# SCH_BlackboxHub_2024-05-23.net
KiCad netlist of a schematic drawn in EasyEDA
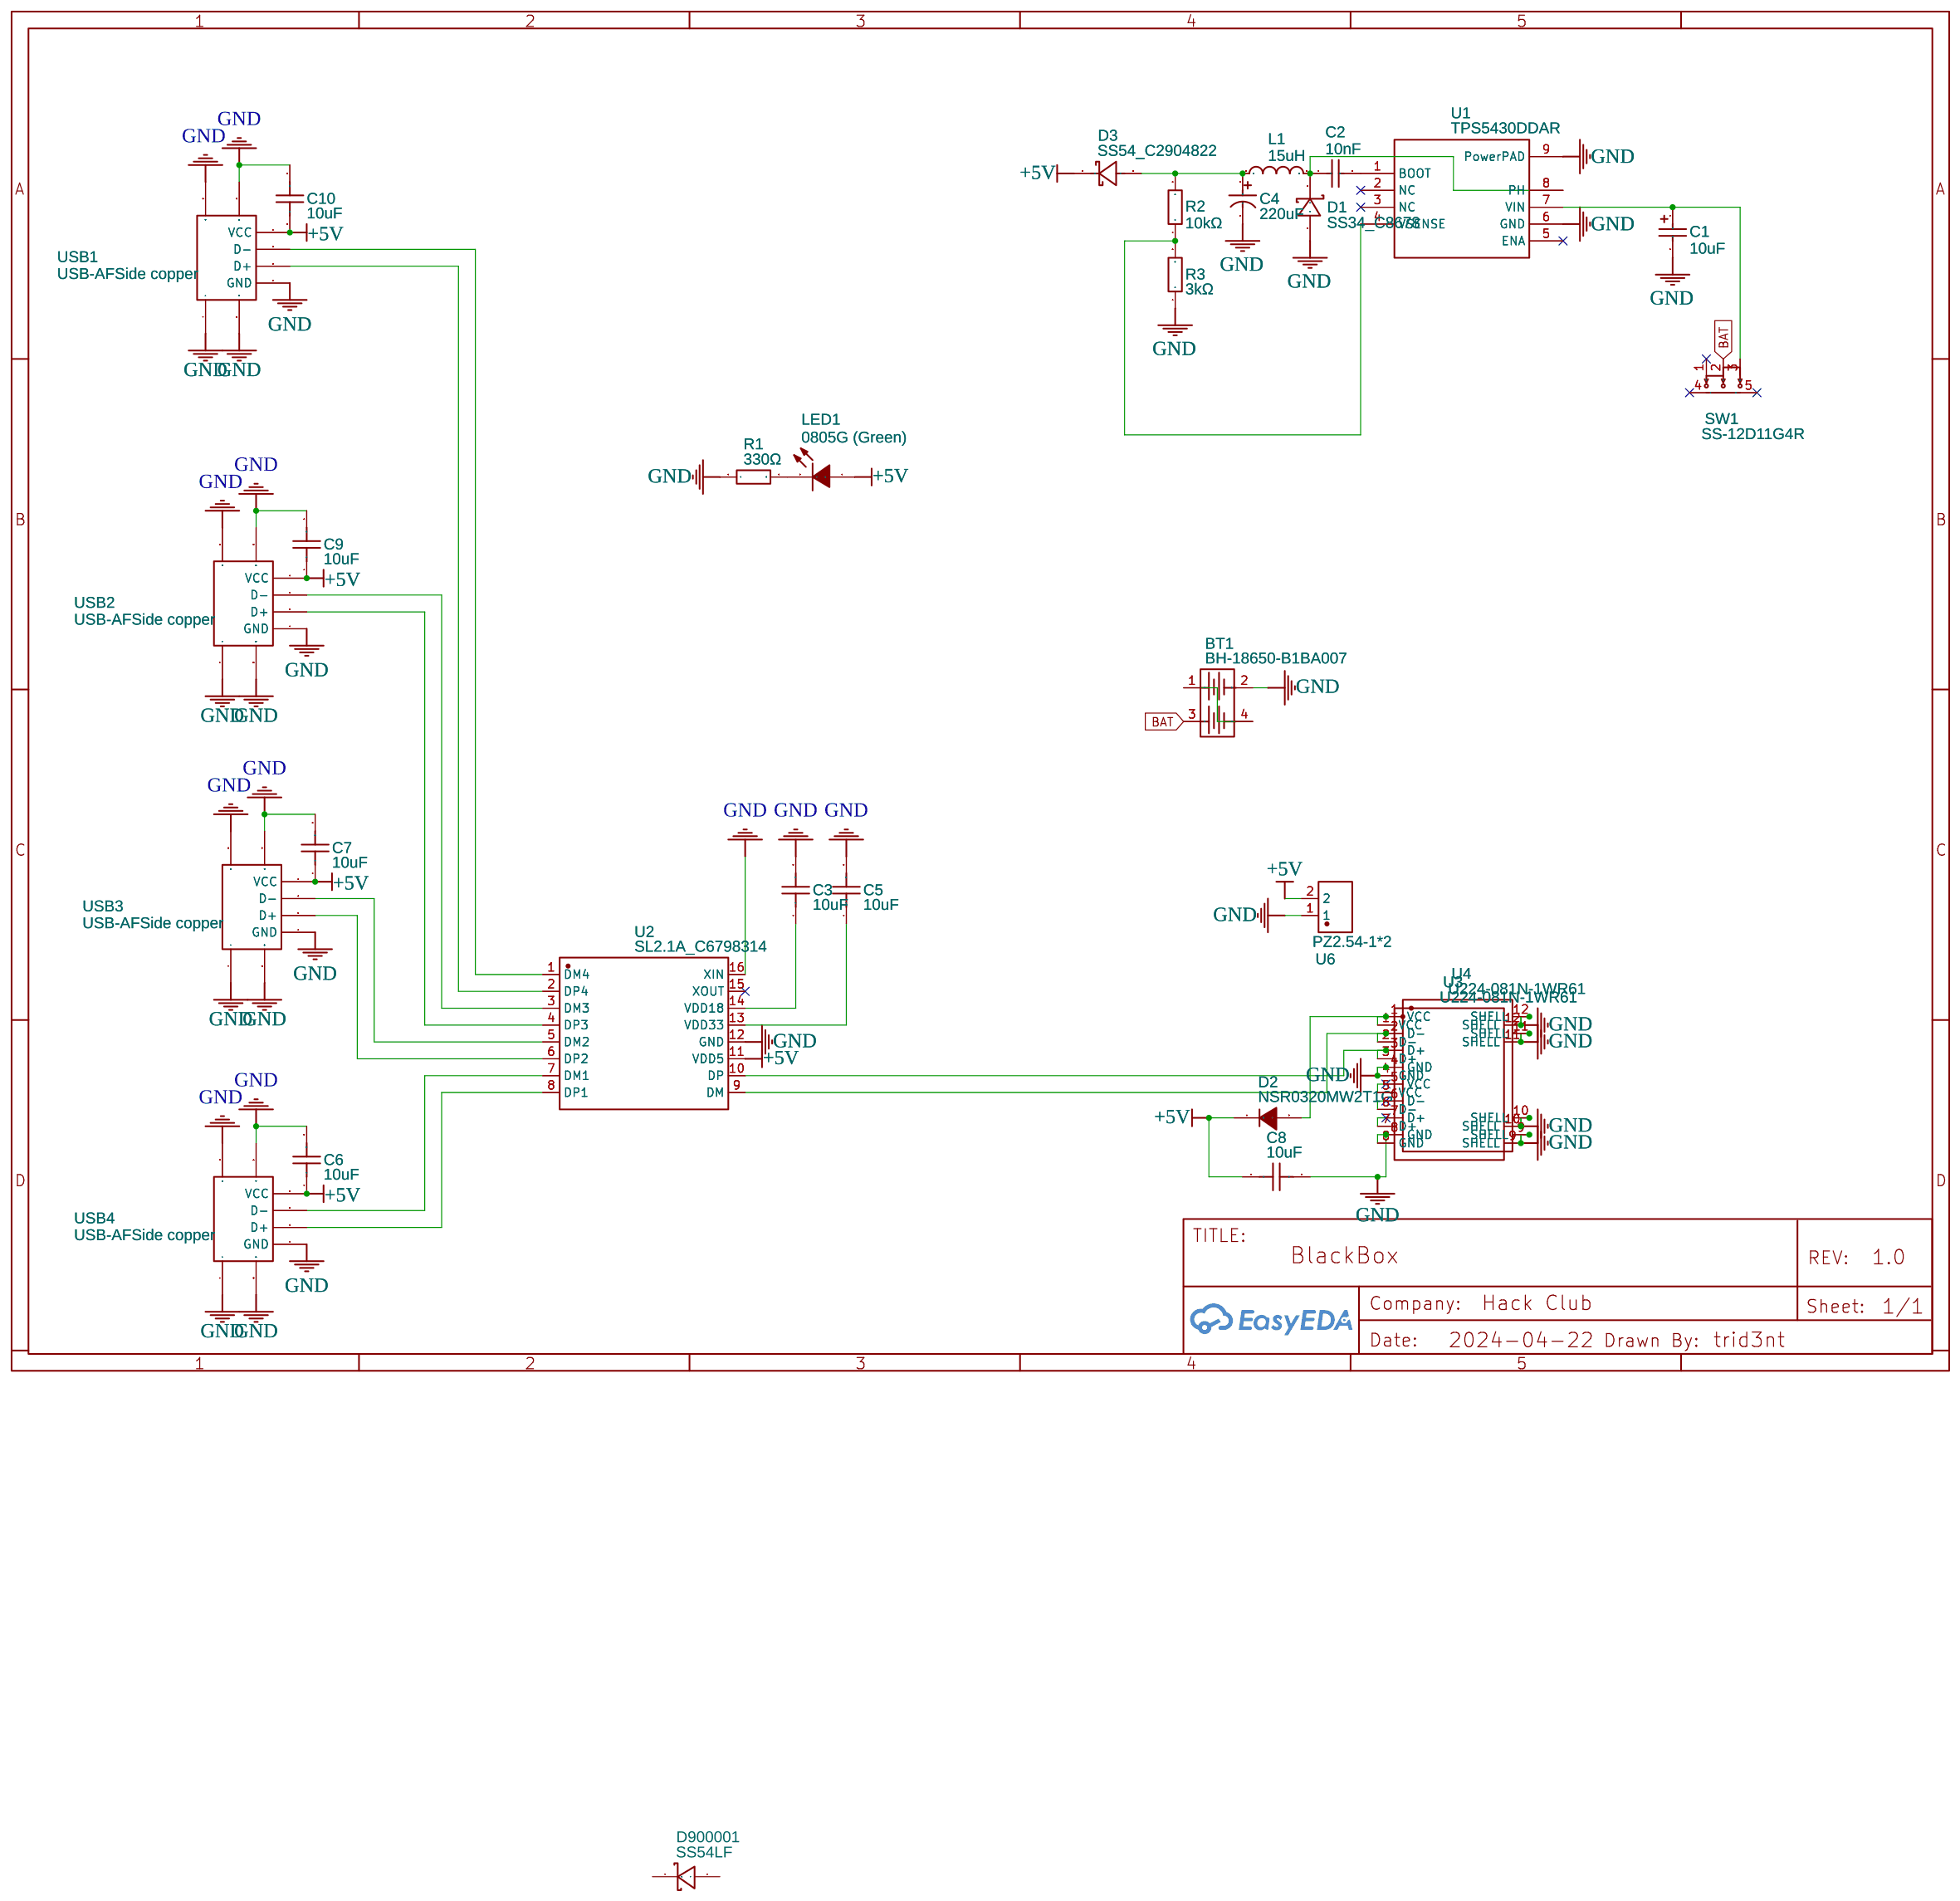
[diagram p0: schematic sheet]

(export (version "E")
  (design (tool "Eeschema 10.0.6"))
  (components
    (comp (ref "BT1")
      (value "BH-18650-B1BA007")
      (fields (field (name "Manufacturer") "MYOUNG(美阳)"))
      (libsource (lib "") (part "BH-18650-B1BA007"))
    )
    (comp (ref "C1")
      (value "10uF")
      (fields (field (name "Manufacturer Part") "TAJA106K016RNJ") (field (name "Manufacturer") "Kyocera AVX"))
      (libsource (lib "") (part "TAJA106K016RNJ"))
    )
    (comp (ref "C2")
      (value "10nF")
      (fields
        (field (name "Manufacturer Part") "CL05B103KB5NNNC")
        (field (name "Manufacturer") "SAMSUNG(三星)")
      )
      (libsource (lib "") (part "CL05B103KB5NNNC"))
    )
    (comp (ref "C3")
      (value "10uF")
      (fields
        (field (name "Manufacturer Part") "CL10A106KP8NNNC")
        (field (name "Manufacturer") "SAMSUNG(三星)")
      )
      (libsource (lib "") (part "CL10A106KP8NNNC"))
    )
    (comp (ref "C4")
      (value "220uF")
      (fields (field (name "Manufacturer Part") "10TPB220M") (field (name "Manufacturer") "PANASONIC(松下)"))
      (libsource (lib "") (part "10TPB220M"))
    )
    (comp (ref "C5")
      (value "10uF")
      (fields
        (field (name "Manufacturer Part") "CL10A106KP8NNNC")
        (field (name "Manufacturer") "SAMSUNG(三星)")
      )
      (libsource (lib "") (part "CL10A106KP8NNNC"))
    )
    (comp (ref "C6")
      (value "10uF")
      (fields
        (field (name "Manufacturer Part") "CL10A106KP8NNNC")
        (field (name "Manufacturer") "SAMSUNG(三星)")
      )
      (libsource (lib "") (part "CL10A106KP8NNNC"))
    )
    (comp (ref "C7")
      (value "10uF")
      (fields
        (field (name "Manufacturer Part") "CL10A106KP8NNNC")
        (field (name "Manufacturer") "SAMSUNG(三星)")
      )
      (libsource (lib "") (part "CL10A106KP8NNNC"))
    )
    (comp (ref "C8")
      (value "10uF")
      (fields
        (field (name "Manufacturer Part") "CL10A106KP8NNNC")
        (field (name "Manufacturer") "SAMSUNG(三星)")
      )
      (libsource (lib "") (part "CL10A106KP8NNNC_1"))
    )
    (comp (ref "C9")
      (value "10uF")
      (fields
        (field (name "Manufacturer Part") "CL10A106KP8NNNC")
        (field (name "Manufacturer") "SAMSUNG(三星)")
      )
      (libsource (lib "") (part "CL10A106KP8NNNC"))
    )
    (comp (ref "C10")
      (value "10uF")
      (fields
        (field (name "Manufacturer Part") "CL10A106KP8NNNC")
        (field (name "Manufacturer") "SAMSUNG(三星)")
      )
      (libsource (lib "") (part "CL10A106KP8NNNC"))
    )
    (comp (ref "D1")
      (value "SS34_C8678")
      (fields (field (name "Manufacturer Part") "SS34") (field (name "Manufacturer") "MDD"))
      (libsource (lib "") (part "SS34_C8678"))
    )
    (comp (ref "D2")
      (value "NSR0320MW2T1G")
      (fields (field (name "Manufacturer") "onsemi(安森美)"))
      (libsource (lib "") (part "NSR0320MW2T1G"))
    )
    (comp (ref "D3")
      (value "SS54_C2904822")
      (fields (field (name "Manufacturer Part") "SS54") (field (name "Manufacturer") "YONGYUTAI(永裕泰)"))
      (libsource (lib "") (part "SS54_C2904822"))
    )
    (comp (ref "D900001")
      (value "SS54LF")
      (fields (field (name "Manufacturer") "晶导微电子"))
      (libsource (lib "") (part "SS54LF"))
    )
    (comp (ref "L1")
      (value "15uH")
      (fields (field (name "Manufacturer Part") "MDA7050-150M") (field (name "Manufacturer") "KOHERelec(科或)"))
      (libsource (lib "") (part "MDA7050-150M"))
    )
    (comp (ref "LED1")
      (value "0805G (Green)")
      (fields (field (name "Manufacturer Part") "KT-0805G") (field (name "Manufacturer") "KENTO"))
      (libsource (lib "") (part "0805G (Green)"))
    )
    (comp (ref "R1")
      (value "330Ω")
      (fields
        (field (name "Manufacturer Part") "0805W8F3300T5E")
        (field (name "Manufacturer") "UNI-ROYAL(厚声)")
      )
      (libsource (lib "") (part "0805W8F3300T5E"))
    )
    (comp (ref "R2")
      (value "10kΩ")
      (fields
        (field (name "Manufacturer Part") "0603WAF1002T5E")
        (field (name "Manufacturer") "UNI-ROYAL(厚声)")
      )
      (libsource (lib "") (part "0603WAF1002T5E"))
    )
    (comp (ref "R3")
      (value "3kΩ")
      (fields
        (field (name "Manufacturer Part") "0603WAF3001T5E")
        (field (name "Manufacturer") "UNI-ROYAL(厚声)")
      )
      (libsource (lib "") (part "0603WAF3001T5E"))
    )
    (comp (ref "SW1")
      (value "SS-12D11G4R")
      (fields (field (name "Manufacturer") "XKB Connectivity(中国星坤)"))
      (libsource (lib "") (part "SS-12D11G4R"))
    )
    (comp (ref "U1")
      (value "TPS5430DDAR")
      (fields (field (name "Manufacturer") "TI(德州仪器)"))
      (libsource (lib "") (part "TPS5430DDAR"))
    )
    (comp (ref "U2")
      (value "SL2.1A_C6798314")
      (fields (field (name "Manufacturer Part") "SL2.1A") (field (name "Manufacturer") "CoreChips(和芯润德)"))
      (libsource (lib "") (part "SL2.1A_C6798314"))
    )
    (comp (ref "U3")
      (value "U224-081N-1WR61")
      (fields (field (name "Manufacturer") "XKB Connectivity(中国星坤)"))
      (libsource (lib "") (part "U224-081N-1WR61"))
    )
    (comp (ref "U4")
      (value "U224-081N-1WR61")
      (fields (field (name "Manufacturer") "XKB Connectivity(中国星坤)"))
      (libsource (lib "") (part "U224-081N-1WR61"))
    )
    (comp (ref "U6")
      (value "PZ2.54-1*2")
      (fields (field (name "Manufacturer") "ZHOURI(洲日)"))
      (libsource (lib "") (part "PZ2.54-1*2"))
    )
    (comp (ref "USB1")
      (value "USB-AFSide copper")
      (fields (field (name "Manufacturer Part") "USB-AF侧插铜") (field (name "Manufacturer") "精拓金"))
      (libsource (lib "") (part "USB-AFSide copper"))
    )
    (comp (ref "USB2")
      (value "USB-AFSide copper")
      (fields (field (name "Manufacturer Part") "USB-AF侧插铜") (field (name "Manufacturer") "精拓金"))
      (libsource (lib "") (part "USB-AFSide copper"))
    )
    (comp (ref "USB3")
      (value "USB-AFSide copper")
      (fields (field (name "Manufacturer Part") "USB-AF侧插铜") (field (name "Manufacturer") "精拓金"))
      (libsource (lib "") (part "USB-AFSide copper"))
    )
    (comp (ref "USB4")
      (value "USB-AFSide copper")
      (fields (field (name "Manufacturer Part") "USB-AF侧插铜") (field (name "Manufacturer") "精拓金"))
      (libsource (lib "") (part "USB-AFSide copper"))
    )
  )
  (nets
    (net (code "1") (name "+5V") (class "Default")
      (node (ref "C10") (pin "1") (pinfunction "1_1") (pintype "unspecified"))
      (node (ref "C6") (pin "1") (pinfunction "1_1") (pintype "unspecified"))
      (node (ref "C7") (pin "1") (pinfunction "1_1") (pintype "unspecified"))
      (node (ref "C8") (pin "1") (pinfunction "1_1") (pintype "unspecified"))
      (node (ref "C9") (pin "1") (pinfunction "1_1") (pintype "unspecified"))
      (node (ref "D2") (pin "1") (pinfunction "C_1") (pintype "unspecified"))
      (node (ref "D3") (pin "1") (pinfunction "K_1") (pintype "unspecified"))
      (node (ref "LED1") (pin "1") (pinfunction "A_1") (pintype "unspecified"))
      (node (ref "U2") (pin "11") (pinfunction "VDD5_11") (pintype "unspecified"))
      (node (ref "U6") (pin "2") (pinfunction "2_2") (pintype "unspecified"))
      (node (ref "USB1") (pin "1") (pinfunction "VCC_1") (pintype "input"))
      (node (ref "USB2") (pin "1") (pinfunction "VCC_1") (pintype "input"))
      (node (ref "USB3") (pin "1") (pinfunction "VCC_1") (pintype "input"))
      (node (ref "USB4") (pin "1") (pinfunction "VCC_1") (pintype "input"))
    )
    (net (code "2") (name "BAT") (class "Default")
      (node (ref "BT1") (pin "3") (pinfunction "3_3") (pintype "input"))
      (node (ref "SW1") (pin "2") (pinfunction "2_2") (pintype "unspecified"))
    )
    (net (code "3") (name "GND") (class "Default")
      (node (ref "BT1") (pin "2") (pinfunction "2_2") (pintype "input"))
      (node (ref "C1") (pin "2") (pinfunction "2_2") (pintype "input"))
      (node (ref "C10") (pin "2") (pinfunction "2_2") (pintype "unspecified"))
      (node (ref "C3") (pin "2") (pinfunction "2_2") (pintype "unspecified"))
      (node (ref "C4") (pin "2") (pinfunction "2_2") (pintype "input"))
      (node (ref "C5") (pin "2") (pinfunction "2_2") (pintype "unspecified"))
      (node (ref "C6") (pin "2") (pinfunction "2_2") (pintype "unspecified"))
      (node (ref "C7") (pin "2") (pinfunction "2_2") (pintype "unspecified"))
      (node (ref "C8") (pin "2") (pinfunction "2_2") (pintype "unspecified"))
      (node (ref "C9") (pin "2") (pinfunction "2_2") (pintype "unspecified"))
      (node (ref "D1") (pin "2") (pinfunction "A_2") (pintype "unspecified"))
      (node (ref "R1") (pin "1") (pinfunction "1_1") (pintype "input"))
      (node (ref "R3") (pin "1") (pinfunction "1_1") (pintype "input"))
      (node (ref "U1") (pin "6") (pinfunction "GND_6") (pintype "unspecified"))
      (node (ref "U1") (pin "9") (pinfunction "PowerPAD_9") (pintype "unspecified"))
      (node (ref "U2") (pin "12") (pinfunction "GND_12") (pintype "unspecified"))
      (node (ref "U2") (pin "16") (pinfunction "XIN_16") (pintype "unspecified"))
      (node (ref "U3") (pin "10") (pinfunction "SHELL_10") (pintype "unspecified"))
      (node (ref "U3") (pin "11") (pinfunction "SHELL_11") (pintype "unspecified"))
      (node (ref "U3") (pin "12") (pinfunction "SHELL_12") (pintype "unspecified"))
      (node (ref "U3") (pin "4") (pinfunction "GND_4") (pintype "unspecified"))
      (node (ref "U3") (pin "8") (pinfunction "GND_8") (pintype "unspecified"))
      (node (ref "U3") (pin "9") (pinfunction "SHELL_9") (pintype "unspecified"))
      (node (ref "U4") (pin "10") (pinfunction "SHELL_10") (pintype "unspecified"))
      (node (ref "U4") (pin "11") (pinfunction "SHELL_11") (pintype "unspecified"))
      (node (ref "U4") (pin "12") (pinfunction "SHELL_12") (pintype "unspecified"))
      (node (ref "U4") (pin "4") (pinfunction "GND_4") (pintype "unspecified"))
      (node (ref "U4") (pin "8") (pinfunction "GND_8") (pintype "unspecified"))
      (node (ref "U4") (pin "9") (pinfunction "SHELL_9") (pintype "unspecified"))
      (node (ref "U6") (pin "1") (pinfunction "1_1") (pintype "unspecified"))
      (node (ref "USB1") (pin "4") (pinfunction "GND_4") (pintype "input"))
      (node (ref "USB1") (pin "5") (pinfunction "5_5") (pintype "unspecified"))
      (node (ref "USB1") (pin "6") (pinfunction "6_6") (pintype "unspecified"))
      (node (ref "USB1") (pin "7") (pinfunction "7_7") (pintype "unspecified"))
      (node (ref "USB1") (pin "8") (pinfunction "8_8") (pintype "unspecified"))
      (node (ref "USB2") (pin "4") (pinfunction "GND_4") (pintype "input"))
      (node (ref "USB2") (pin "5") (pinfunction "5_5") (pintype "unspecified"))
      (node (ref "USB2") (pin "6") (pinfunction "6_6") (pintype "unspecified"))
      (node (ref "USB2") (pin "7") (pinfunction "7_7") (pintype "unspecified"))
      (node (ref "USB2") (pin "8") (pinfunction "8_8") (pintype "unspecified"))
      (node (ref "USB3") (pin "4") (pinfunction "GND_4") (pintype "input"))
      (node (ref "USB3") (pin "5") (pinfunction "5_5") (pintype "unspecified"))
      (node (ref "USB3") (pin "6") (pinfunction "6_6") (pintype "unspecified"))
      (node (ref "USB3") (pin "7") (pinfunction "7_7") (pintype "unspecified"))
      (node (ref "USB3") (pin "8") (pinfunction "8_8") (pintype "unspecified"))
      (node (ref "USB4") (pin "4") (pinfunction "GND_4") (pintype "input"))
      (node (ref "USB4") (pin "5") (pinfunction "5_5") (pintype "unspecified"))
      (node (ref "USB4") (pin "6") (pinfunction "6_6") (pintype "unspecified"))
      (node (ref "USB4") (pin "7") (pinfunction "7_7") (pintype "unspecified"))
      (node (ref "USB4") (pin "8") (pinfunction "8_8") (pintype "unspecified"))
    )
    (net (code "4") (name "Net-(BT1-Pad1)") (class "Default")
      (node (ref "BT1") (pin "1") (pinfunction "1_1") (pintype "input"))
      (node (ref "BT1") (pin "4") (pinfunction "4_4") (pintype "input"))
    )
    (net (code "5") (name "Net-(D1-K)") (class "Default")
      (node (ref "C2") (pin "1") (pinfunction "1_1") (pintype "input"))
      (node (ref "D1") (pin "1") (pinfunction "K_1") (pintype "unspecified"))
      (node (ref "L1") (pin "2") (pinfunction "2_2") (pintype "unspecified"))
      (node (ref "U1") (pin "8") (pinfunction "PH_8") (pintype "unspecified"))
    )
    (net (code "6") (name "Net-(D2-A)") (class "Default")
      (node (ref "D2") (pin "2") (pinfunction "A_2") (pintype "unspecified"))
      (node (ref "U3") (pin "1") (pinfunction "VCC_1") (pintype "unspecified"))
      (node (ref "U4") (pin "1") (pinfunction "VCC_1") (pintype "unspecified"))
    )
    (net (code "7") (name "Net-(D3-A)") (class "Default")
      (node (ref "C4") (pin "1") (pinfunction "1_1") (pintype "input"))
      (node (ref "D3") (pin "2") (pinfunction "A_2") (pintype "unspecified"))
      (node (ref "L1") (pin "1") (pinfunction "1_1") (pintype "unspecified"))
      (node (ref "R2") (pin "2") (pinfunction "2_2") (pintype "input"))
    )
    (net (code "8") (name "Net-(LED1-K)") (class "Default")
      (node (ref "LED1") (pin "2") (pinfunction "K_2") (pintype "unspecified"))
      (node (ref "R1") (pin "2") (pinfunction "2_2") (pintype "input"))
    )
    (net (code "9") (name "Net-(U1-BOOT)") (class "Default")
      (node (ref "C2") (pin "2") (pinfunction "2_2") (pintype "input"))
      (node (ref "U1") (pin "1") (pinfunction "BOOT_1") (pintype "unspecified"))
    )
    (net (code "10") (name "Net-(U1-VIN)") (class "Default")
      (node (ref "C1") (pin "1") (pinfunction "1_1") (pintype "input"))
      (node (ref "SW1") (pin "3") (pinfunction "3_3") (pintype "unspecified"))
      (node (ref "U1") (pin "7") (pinfunction "VIN_7") (pintype "unspecified"))
    )
    (net (code "11") (name "Net-(U1-VSENSE)") (class "Default")
      (node (ref "R2") (pin "1") (pinfunction "1_1") (pintype "input"))
      (node (ref "R3") (pin "2") (pinfunction "2_2") (pintype "input"))
      (node (ref "U1") (pin "4") (pinfunction "VSENSE_4") (pintype "unspecified"))
    )
    (net (code "12") (name "Net-(U2-DM)") (class "Default")
      (node (ref "U2") (pin "9") (pinfunction "DM_9") (pintype "unspecified"))
      (node (ref "U3") (pin "2") (pinfunction "D-_2") (pintype "unspecified"))
      (node (ref "U4") (pin "2") (pinfunction "D-_2") (pintype "unspecified"))
    )
    (net (code "13") (name "Net-(U2-DM1)") (class "Default")
      (node (ref "U2") (pin "7") (pinfunction "DM1_7") (pintype "unspecified"))
      (node (ref "USB4") (pin "2") (pinfunction "D-_2") (pintype "input"))
    )
    (net (code "14") (name "Net-(U2-DM2)") (class "Default")
      (node (ref "U2") (pin "5") (pinfunction "DM2_5") (pintype "unspecified"))
      (node (ref "USB3") (pin "2") (pinfunction "D-_2") (pintype "input"))
    )
    (net (code "15") (name "Net-(U2-DM3)") (class "Default")
      (node (ref "U2") (pin "3") (pinfunction "DM3_3") (pintype "unspecified"))
      (node (ref "USB2") (pin "2") (pinfunction "D-_2") (pintype "input"))
    )
    (net (code "16") (name "Net-(U2-DM4)") (class "Default")
      (node (ref "U2") (pin "1") (pinfunction "DM4_1") (pintype "unspecified"))
      (node (ref "USB1") (pin "2") (pinfunction "D-_2") (pintype "input"))
    )
    (net (code "17") (name "Net-(U2-DP)") (class "Default")
      (node (ref "U2") (pin "10") (pinfunction "DP_10") (pintype "unspecified"))
      (node (ref "U3") (pin "3") (pinfunction "D+_3") (pintype "unspecified"))
      (node (ref "U4") (pin "3") (pinfunction "D+_3") (pintype "unspecified"))
    )
    (net (code "18") (name "Net-(U2-DP1)") (class "Default")
      (node (ref "U2") (pin "8") (pinfunction "DP1_8") (pintype "unspecified"))
      (node (ref "USB4") (pin "3") (pinfunction "D+_3") (pintype "input"))
    )
    (net (code "19") (name "Net-(U2-DP2)") (class "Default")
      (node (ref "U2") (pin "6") (pinfunction "DP2_6") (pintype "unspecified"))
      (node (ref "USB3") (pin "3") (pinfunction "D+_3") (pintype "input"))
    )
    (net (code "20") (name "Net-(U2-DP3)") (class "Default")
      (node (ref "U2") (pin "4") (pinfunction "DP3_4") (pintype "unspecified"))
      (node (ref "USB2") (pin "3") (pinfunction "D+_3") (pintype "input"))
    )
    (net (code "21") (name "Net-(U2-DP4)") (class "Default")
      (node (ref "U2") (pin "2") (pinfunction "DP4_2") (pintype "unspecified"))
      (node (ref "USB1") (pin "3") (pinfunction "D+_3") (pintype "input"))
    )
    (net (code "22") (name "Net-(U2-VDD18)") (class "Default")
      (node (ref "C3") (pin "1") (pinfunction "1_1") (pintype "unspecified"))
      (node (ref "U2") (pin "14") (pinfunction "VDD18_14") (pintype "unspecified"))
    )
    (net (code "23") (name "Net-(U2-VDD33)") (class "Default")
      (node (ref "C5") (pin "1") (pinfunction "1_1") (pintype "unspecified"))
      (node (ref "U2") (pin "13") (pinfunction "VDD33_13") (pintype "unspecified"))
    )
    (net (code "24") (name "unconnected-(D900001-A-Pad2)") (class "Default")
      (node (ref "D900001") (pin "2") (pinfunction "A_2") (pintype "unspecified"))
    )
    (net (code "25") (name "unconnected-(D900001-C-Pad1)") (class "Default")
      (node (ref "D900001") (pin "1") (pinfunction "C_1") (pintype "unspecified"))
    )
    (net (code "26") (name "unconnected-(SW1-Pad1)") (class "Default")
      (node (ref "SW1") (pin "1") (pinfunction "1_1") (pintype "unspecified+no_connect"))
    )
    (net (code "27") (name "unconnected-(SW1-Pad4)") (class "Default")
      (node (ref "SW1") (pin "4") (pinfunction "4_4") (pintype "unspecified+no_connect"))
    )
    (net (code "28") (name "unconnected-(SW1-Pad5)") (class "Default")
      (node (ref "SW1") (pin "5") (pinfunction "5_5") (pintype "unspecified+no_connect"))
    )
    (net (code "29") (name "unconnected-(U1-ENA-Pad5)") (class "Default")
      (node (ref "U1") (pin "5") (pinfunction "ENA_5") (pintype "unspecified+no_connect"))
    )
    (net (code "30") (name "unconnected-(U1-NC-Pad2)") (class "Default")
      (node (ref "U1") (pin "2") (pinfunction "NC_2") (pintype "unspecified+no_connect"))
    )
    (net (code "31") (name "unconnected-(U1-NC-Pad3)") (class "Default")
      (node (ref "U1") (pin "3") (pinfunction "NC_3") (pintype "unspecified+no_connect"))
    )
    (net (code "32") (name "unconnected-(U2-XOUT-Pad15)") (class "Default")
      (node (ref "U2") (pin "15") (pinfunction "XOUT_15") (pintype "unspecified+no_connect"))
    )
    (net (code "33") (name "unconnected-(U3-D+-Pad7)") (class "Default")
      (node (ref "U3") (pin "7") (pinfunction "D+_7") (pintype "unspecified"))
      (node (ref "U4") (pin "7") (pinfunction "D+_7") (pintype "unspecified"))
    )
    (net (code "34") (name "unconnected-(U3-D--Pad6)") (class "Default")
      (node (ref "U3") (pin "6") (pinfunction "D-_6") (pintype "unspecified"))
      (node (ref "U4") (pin "6") (pinfunction "D-_6") (pintype "unspecified"))
    )
    (net (code "35") (name "unconnected-(U3-VCC-Pad5)") (class "Default")
      (node (ref "U3") (pin "5") (pinfunction "VCC_5") (pintype "unspecified"))
      (node (ref "U4") (pin "5") (pinfunction "VCC_5") (pintype "unspecified"))
    )
  )
)
